# CONNECTEUR_2.net
KiCad netlist of a schematic drawn in Altium Designer
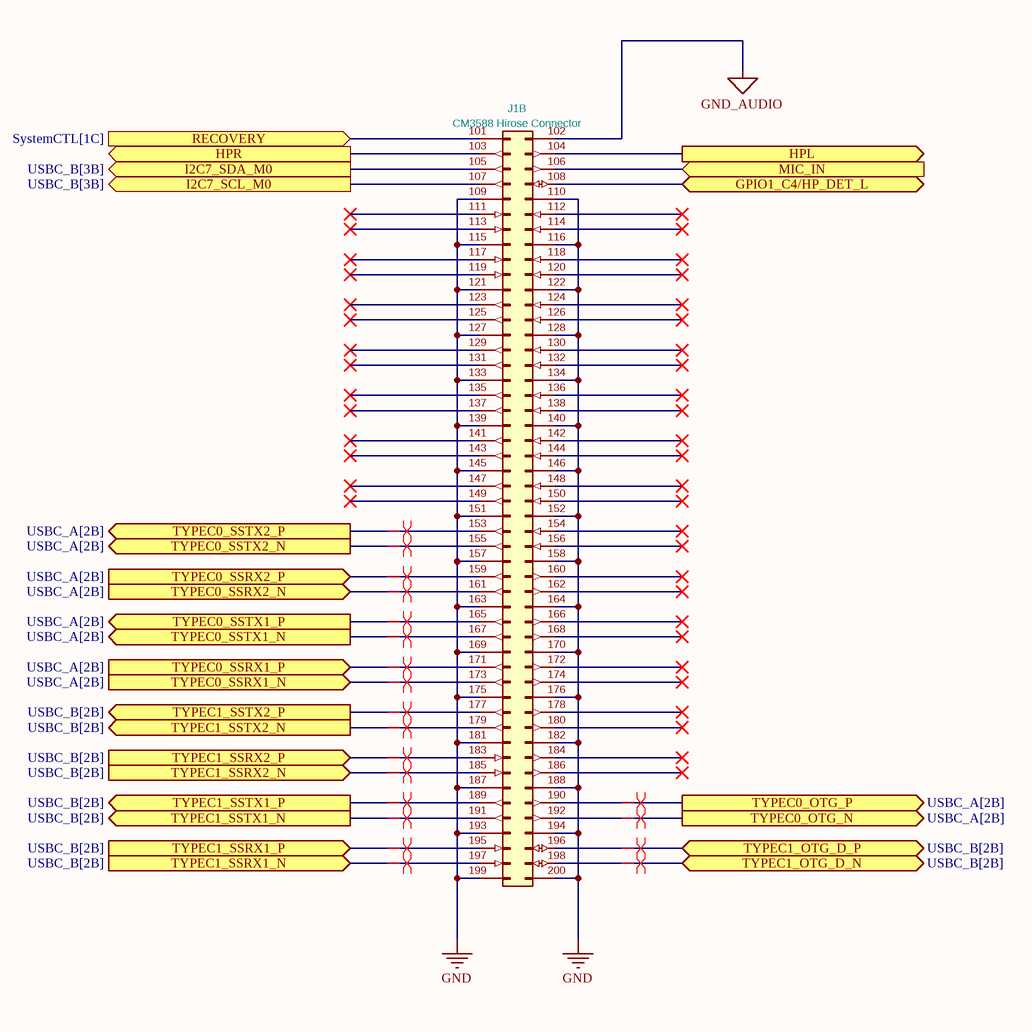
[diagram p0: CONNECTEUR_2.SchDoc, middle]

(export (version "E")
  (design (tool "Eeschema 10.0.6"))
  (components
    (comp (ref "J1")
      (value "CM3588 Hirose Connector")
      (footprint "CM3588")
      (libsource (lib "cm3588") (part "CM3588"))
    )
  )
  (nets
    (net (code "1") (name "/GPIO1_C4{slash}HP_DET_L") (class "Default")
      (node (ref "J1") (pin "108") (pinfunction "GPIO1_C4/HP_DET_L_108") (pintype "bidirectional"))
    )
    (net (code "2") (name "/HPL") (class "Default")
      (node (ref "J1") (pin "104") (pinfunction "HPL_104") (pintype "output"))
    )
    (net (code "3") (name "/HPR") (class "Default")
      (node (ref "J1") (pin "103") (pinfunction "HPR_103") (pintype "output"))
    )
    (net (code "4") (name "/I2C7_SCL_M0") (class "Default")
      (node (ref "J1") (pin "107") (pinfunction "I2C7_SCL_M0_107") (pintype "output"))
    )
    (net (code "5") (name "/I2C7_SDA_M0") (class "Default")
      (node (ref "J1") (pin "105") (pinfunction "I2C7_SDA_M0_105") (pintype "output"))
    )
    (net (code "6") (name "/MIC_IN") (class "Default")
      (node (ref "J1") (pin "106") (pinfunction "MIC_IN_106") (pintype "output"))
    )
    (net (code "7") (name "/RECOVERY") (class "Default")
      (node (ref "J1") (pin "101") (pinfunction "RECOVERY_101") (pintype "passive"))
    )
    (net (code "8") (name "/TYPEC0_OTG_N") (class "Default")
      (node (ref "J1") (pin "192") (pinfunction "TYPEC0_OTG_DM_192") (pintype "output"))
    )
    (net (code "9") (name "/TYPEC0_OTG_P") (class "Default")
      (node (ref "J1") (pin "190") (pinfunction "TYPEC0_OTG_DP_190") (pintype "output"))
    )
    (net (code "10") (name "/TYPEC0_SSRX1_N") (class "Default")
      (node (ref "J1") (pin "173") (pinfunction "TYPEC0_SSRX1N_173") (pintype "output"))
    )
    (net (code "11") (name "/TYPEC0_SSRX1_P") (class "Default")
      (node (ref "J1") (pin "171") (pinfunction "TYPEC0_SSRX1P_171") (pintype "output"))
    )
    (net (code "12") (name "/TYPEC0_SSRX2_N") (class "Default")
      (node (ref "J1") (pin "161") (pinfunction "TYPEC0_SSRX2N_161") (pintype "output"))
    )
    (net (code "13") (name "/TYPEC0_SSRX2_P") (class "Default")
      (node (ref "J1") (pin "159") (pinfunction "TYPEC0_SSRX2P_159") (pintype "output"))
    )
    (net (code "14") (name "/TYPEC0_SSTX1_N") (class "Default")
      (node (ref "J1") (pin "167") (pinfunction "TYPEC0_SSTX1N_167") (pintype "output"))
    )
    (net (code "15") (name "/TYPEC0_SSTX1_P") (class "Default")
      (node (ref "J1") (pin "165") (pinfunction "TYPEC0_SSTX1P_165") (pintype "output"))
    )
    (net (code "16") (name "/TYPEC0_SSTX2_N") (class "Default")
      (node (ref "J1") (pin "155") (pinfunction "TYPEC0_SSTX2N_155") (pintype "output"))
    )
    (net (code "17") (name "/TYPEC0_SSTX2_P") (class "Default")
      (node (ref "J1") (pin "153") (pinfunction "TYPEC0_SSTX2P_153") (pintype "output"))
    )
    (net (code "18") (name "/TYPEC1_OTG_D_N") (class "Default")
      (node (ref "J1") (pin "198") (pinfunction "TYPEC1_OTG_DM_198") (pintype "bidirectional"))
    )
    (net (code "19") (name "/TYPEC1_OTG_D_P") (class "Default")
      (node (ref "J1") (pin "196") (pinfunction "TYPEC1_OTG_DP_196") (pintype "bidirectional"))
    )
    (net (code "20") (name "/TYPEC1_SSRX1_N") (class "Default")
      (node (ref "J1") (pin "197") (pinfunction "TYPEC1_SSRX1N_197") (pintype "input"))
    )
    (net (code "21") (name "/TYPEC1_SSRX1_P") (class "Default")
      (node (ref "J1") (pin "195") (pinfunction "TYPEC1_SSRX1P_195") (pintype "input"))
    )
    (net (code "22") (name "/TYPEC1_SSRX2_N") (class "Default")
      (node (ref "J1") (pin "185") (pinfunction "TYPEC1_SSRX2N_185") (pintype "input"))
    )
    (net (code "23") (name "/TYPEC1_SSRX2_P") (class "Default")
      (node (ref "J1") (pin "183") (pinfunction "TYPEC1_SSRX2P_183") (pintype "input"))
    )
    (net (code "24") (name "/TYPEC1_SSTX1_N") (class "Default")
      (node (ref "J1") (pin "191") (pinfunction "TYPEC1_SSTX1N_191") (pintype "output"))
    )
    (net (code "25") (name "/TYPEC1_SSTX1_P") (class "Default")
      (node (ref "J1") (pin "189") (pinfunction "TYPEC1_SSTX1P_189") (pintype "output"))
    )
    (net (code "26") (name "/TYPEC1_SSTX2_N") (class "Default")
      (node (ref "J1") (pin "179") (pinfunction "TYPEC1_SSTX2N_179") (pintype "output"))
    )
    (net (code "27") (name "/TYPEC1_SSTX2_P") (class "Default")
      (node (ref "J1") (pin "177") (pinfunction "TYPEC1_SSTX2P_177") (pintype "output"))
    )
    (net (code "28") (name "GND") (class "Default")
      (node (ref "J1") (pin "109") (pinfunction "GND_109") (pintype "passive"))
      (node (ref "J1") (pin "110") (pinfunction "GND_110") (pintype "passive"))
      (node (ref "J1") (pin "115") (pinfunction "GND_115") (pintype "passive"))
      (node (ref "J1") (pin "116") (pinfunction "GND_116") (pintype "passive"))
      (node (ref "J1") (pin "121") (pinfunction "GND_121") (pintype "passive"))
      (node (ref "J1") (pin "122") (pinfunction "GND_122") (pintype "passive"))
      (node (ref "J1") (pin "127") (pinfunction "GND_127") (pintype "passive"))
      (node (ref "J1") (pin "128") (pinfunction "GND_128") (pintype "passive"))
      (node (ref "J1") (pin "133") (pinfunction "GND_133") (pintype "passive"))
      (node (ref "J1") (pin "134") (pinfunction "GND_134") (pintype "passive"))
      (node (ref "J1") (pin "139") (pinfunction "GND_139") (pintype "passive"))
      (node (ref "J1") (pin "140") (pinfunction "GND_140") (pintype "passive"))
      (node (ref "J1") (pin "145") (pinfunction "GND_145") (pintype "passive"))
      (node (ref "J1") (pin "146") (pinfunction "GND_146") (pintype "passive"))
      (node (ref "J1") (pin "151") (pinfunction "GND_151") (pintype "passive"))
      (node (ref "J1") (pin "152") (pinfunction "GND_152") (pintype "passive"))
      (node (ref "J1") (pin "157") (pinfunction "GND_157") (pintype "passive"))
      (node (ref "J1") (pin "158") (pinfunction "GND_158") (pintype "passive"))
      (node (ref "J1") (pin "163") (pinfunction "GND_163") (pintype "passive"))
      (node (ref "J1") (pin "164") (pinfunction "GND_164") (pintype "passive"))
      (node (ref "J1") (pin "169") (pinfunction "GND_169") (pintype "passive"))
      (node (ref "J1") (pin "170") (pinfunction "GND_170") (pintype "passive"))
      (node (ref "J1") (pin "175") (pinfunction "GND_175") (pintype "passive"))
      (node (ref "J1") (pin "176") (pinfunction "GND_176") (pintype "passive"))
      (node (ref "J1") (pin "181") (pinfunction "GND_181") (pintype "passive"))
      (node (ref "J1") (pin "182") (pinfunction "GND_182") (pintype "passive"))
      (node (ref "J1") (pin "187") (pinfunction "GND_187") (pintype "passive"))
      (node (ref "J1") (pin "188") (pinfunction "GND_188") (pintype "passive"))
      (node (ref "J1") (pin "193") (pinfunction "GND_193") (pintype "passive"))
      (node (ref "J1") (pin "194") (pinfunction "GND_194") (pintype "passive"))
      (node (ref "J1") (pin "199") (pinfunction "GND_199") (pintype "passive"))
      (node (ref "J1") (pin "200") (pinfunction "GND_200") (pintype "passive"))
    )
    (net (code "29") (name "GND_AUDIO") (class "Default")
      (node (ref "J1") (pin "102") (pinfunction "GND_AUDUO_102") (pintype "passive"))
    )
    (net (code "30") (name "unconnected-(J1B-MIPI_DPHY0_RX_CLKN-Pad120)") (class "Default")
      (node (ref "J1") (pin "120") (pinfunction "MIPI_DPHY0_RX_CLKN_120") (pintype "input+no_connect"))
    )
    (net (code "31") (name "unconnected-(J1B-MIPI_DPHY0_RX_CLKP-Pad118)") (class "Default")
      (node (ref "J1") (pin "118") (pinfunction "MIPI_DPHY0_RX_CLKP_118") (pintype "input+no_connect"))
    )
    (net (code "32") (name "unconnected-(J1B-MIPI_DPHY0_RX_D0N-Pad126)") (class "Default")
      (node (ref "J1") (pin "126") (pinfunction "MIPI_DPHY0_RX_D0N_126") (pintype "input+no_connect"))
    )
    (net (code "33") (name "unconnected-(J1B-MIPI_DPHY0_RX_D0P-Pad124)") (class "Default")
      (node (ref "J1") (pin "124") (pinfunction "MIPI_DPHY0_RX_D0P_124") (pintype "input+no_connect"))
    )
    (net (code "34") (name "unconnected-(J1B-MIPI_DPHY0_RX_D1N-Pad119)") (class "Default")
      (node (ref "J1") (pin "119") (pinfunction "MIPI_DPHY0_RX_D1N_119") (pintype "input+no_connect"))
    )
    (net (code "35") (name "unconnected-(J1B-MIPI_DPHY0_RX_D1P-Pad117)") (class "Default")
      (node (ref "J1") (pin "117") (pinfunction "MIPI_DPHY0_RX_D1P_117") (pintype "input+no_connect"))
    )
    (net (code "36") (name "unconnected-(J1B-MIPI_DPHY0_RX_D2N-Pad113)") (class "Default")
      (node (ref "J1") (pin "113") (pinfunction "MIPI_DPHY0_RX_D2N_113") (pintype "input+no_connect"))
    )
    (net (code "37") (name "unconnected-(J1B-MIPI_DPHY0_RX_D2P-Pad111)") (class "Default")
      (node (ref "J1") (pin "111") (pinfunction "MIPI_DPHY0_RX_D2P_111") (pintype "input+no_connect"))
    )
    (net (code "38") (name "unconnected-(J1B-MIPI_DPHY0_RX_D3N-Pad114)") (class "Default")
      (node (ref "J1") (pin "114") (pinfunction "MIPI_DPHY0_RX_D3N_114") (pintype "input+no_connect"))
    )
    (net (code "39") (name "unconnected-(J1B-MIPI_DPHY0_RX_D3P-Pad112)") (class "Default")
      (node (ref "J1") (pin "112") (pinfunction "MIPI_DPHY0_RX_D3P_112") (pintype "input+no_connect"))
    )
    (net (code "40") (name "unconnected-(J1B-MIPI_DPHY0_TX_CLKN-Pad137)") (class "Default")
      (node (ref "J1") (pin "137") (pinfunction "MIPI_DPHY0_TX_CLKN_137") (pintype "output+no_connect"))
    )
    (net (code "41") (name "unconnected-(J1B-MIPI_DPHY0_TX_CLKP-Pad135)") (class "Default")
      (node (ref "J1") (pin "135") (pinfunction "MIPI_DPHY0_TX_CLKP_135") (pintype "output+no_connect"))
    )
    (net (code "42") (name "unconnected-(J1B-MIPI_DPHY0_TX_D0N-Pad149)") (class "Default")
      (node (ref "J1") (pin "149") (pinfunction "MIPI_DPHY0_TX_D0N_149") (pintype "output+no_connect"))
    )
    (net (code "43") (name "unconnected-(J1B-MIPI_DPHY0_TX_D0P-Pad147)") (class "Default")
      (node (ref "J1") (pin "147") (pinfunction "MIPI_DPHY0_TX_D0P_147") (pintype "output+no_connect"))
    )
    (net (code "44") (name "unconnected-(J1B-MIPI_DPHY0_TX_D1N-Pad143)") (class "Default")
      (node (ref "J1") (pin "143") (pinfunction "MIPI_DPHY0_TX_D1N_143") (pintype "output+no_connect"))
    )
    (net (code "45") (name "unconnected-(J1B-MIPI_DPHY0_TX_D1P-Pad141)") (class "Default")
      (node (ref "J1") (pin "141") (pinfunction "MIPI_DPHY0_TX_D1P_141") (pintype "output+no_connect"))
    )
    (net (code "46") (name "unconnected-(J1B-MIPI_DPHY0_TX_D2N-Pad131)") (class "Default")
      (node (ref "J1") (pin "131") (pinfunction "MIPI_DPHY0_TX_D2N_131") (pintype "output+no_connect"))
    )
    (net (code "47") (name "unconnected-(J1B-MIPI_DPHY0_TX_D2P-Pad129)") (class "Default")
      (node (ref "J1") (pin "129") (pinfunction "MIPI_DPHY0_TX_D2P_129") (pintype "output+no_connect"))
    )
    (net (code "48") (name "unconnected-(J1B-MIPI_DPHY0_TX_D3N-Pad125)") (class "Default")
      (node (ref "J1") (pin "125") (pinfunction "MIPI_DPHY0_TX_D3N_125") (pintype "output+no_connect"))
    )
    (net (code "49") (name "unconnected-(J1B-MIPI_DPHY0_TX_D3P-Pad123)") (class "Default")
      (node (ref "J1") (pin "123") (pinfunction "MIPI_DPHY0_TX_D3P_123") (pintype "output+no_connect"))
    )
    (net (code "50") (name "unconnected-(J1B-MIPI_DPHY1_RX_CLKN-Pad144)") (class "Default")
      (node (ref "J1") (pin "144") (pinfunction "MIPI_DPHY1_RX_CLKN_144") (pintype "input+no_connect"))
    )
    (net (code "51") (name "unconnected-(J1B-MIPI_DPHY1_RX_CLKP-Pad142)") (class "Default")
      (node (ref "J1") (pin "142") (pinfunction "MIPI_DPHY1_RX_CLKP_142") (pintype "input+no_connect"))
    )
    (net (code "52") (name "unconnected-(J1B-MIPI_DPHY1_RX_D0N-Pad156)") (class "Default")
      (node (ref "J1") (pin "156") (pinfunction "MIPI_DPHY1_RX_D0N_156") (pintype "input+no_connect"))
    )
    (net (code "53") (name "unconnected-(J1B-MIPI_DPHY1_RX_D0P-Pad154)") (class "Default")
      (node (ref "J1") (pin "154") (pinfunction "MIPI_DPHY1_RX_D0P_154") (pintype "input+no_connect"))
    )
    (net (code "54") (name "unconnected-(J1B-MIPI_DPHY1_RX_D1N-Pad150)") (class "Default")
      (node (ref "J1") (pin "150") (pinfunction "MIPI_DPHY1_RX_D1N_150") (pintype "input+no_connect"))
    )
    (net (code "55") (name "unconnected-(J1B-MIPI_DPHY1_RX_D1P-Pad148)") (class "Default")
      (node (ref "J1") (pin "148") (pinfunction "MIPI_DPHY1_RX_D1P_148") (pintype "input+no_connect"))
    )
    (net (code "56") (name "unconnected-(J1B-MIPI_DPHY1_RX_D2N-Pad138)") (class "Default")
      (node (ref "J1") (pin "138") (pinfunction "MIPI_DPHY1_RX_D2N_138") (pintype "input+no_connect"))
    )
    (net (code "57") (name "unconnected-(J1B-MIPI_DPHY1_RX_D2P-Pad136)") (class "Default")
      (node (ref "J1") (pin "136") (pinfunction "MIPI_DPHY1_RX_D2P_136") (pintype "input+no_connect"))
    )
    (net (code "58") (name "unconnected-(J1B-MIPI_DPHY1_RX_D3N-Pad132)") (class "Default")
      (node (ref "J1") (pin "132") (pinfunction "MIPI_DPHY1_RX_D3N_132") (pintype "input+no_connect"))
    )
    (net (code "59") (name "unconnected-(J1B-MIPI_DPHY1_RX_D3P-Pad130)") (class "Default")
      (node (ref "J1") (pin "130") (pinfunction "MIPI_DPHY1_RX_D3P_130") (pintype "input+no_connect"))
    )
    (net (code "60") (name "unconnected-(J1B-MIPI_DPHY1_TX_CLKN-Pad174)") (class "Default")
      (node (ref "J1") (pin "174") (pinfunction "MIPI_DPHY1_TX_CLKN_174") (pintype "output+no_connect"))
    )
    (net (code "61") (name "unconnected-(J1B-MIPI_DPHY1_TX_CLKP-Pad172)") (class "Default")
      (node (ref "J1") (pin "172") (pinfunction "MIPI_DPHY1_TX_CLKP_172") (pintype "output+no_connect"))
    )
    (net (code "62") (name "unconnected-(J1B-MIPI_DPHY1_TX_D0N-Pad186)") (class "Default")
      (node (ref "J1") (pin "186") (pinfunction "MIPI_DPHY1_TX_D0N_186") (pintype "output+no_connect"))
    )
    (net (code "63") (name "unconnected-(J1B-MIPI_DPHY1_TX_D0P-Pad184)") (class "Default")
      (node (ref "J1") (pin "184") (pinfunction "MIPI_DPHY1_TX_D0P_184") (pintype "output+no_connect"))
    )
    (net (code "64") (name "unconnected-(J1B-MIPI_DPHY1_TX_D1N-Pad180)") (class "Default")
      (node (ref "J1") (pin "180") (pinfunction "MIPI_DPHY1_TX_D1N_180") (pintype "output+no_connect"))
    )
    (net (code "65") (name "unconnected-(J1B-MIPI_DPHY1_TX_D1P-Pad178)") (class "Default")
      (node (ref "J1") (pin "178") (pinfunction "MIPI_DPHY1_TX_D1P_178") (pintype "output+no_connect"))
    )
    (net (code "66") (name "unconnected-(J1B-MIPI_DPHY1_TX_D2N-Pad168)") (class "Default")
      (node (ref "J1") (pin "168") (pinfunction "MIPI_DPHY1_TX_D2N_168") (pintype "output+no_connect"))
    )
    (net (code "67") (name "unconnected-(J1B-MIPI_DPHY1_TX_D2P-Pad166)") (class "Default")
      (node (ref "J1") (pin "166") (pinfunction "MIPI_DPHY1_TX_D2P_166") (pintype "output+no_connect"))
    )
    (net (code "68") (name "unconnected-(J1B-MIPI_DPHY1_TX_D3N-Pad162)") (class "Default")
      (node (ref "J1") (pin "162") (pinfunction "MIPI_DPHY1_TX_D3N_162") (pintype "output+no_connect"))
    )
    (net (code "69") (name "unconnected-(J1B-MIPI_DPHY1_TX_D3P-Pad160)") (class "Default")
      (node (ref "J1") (pin "160") (pinfunction "MIPI_DPHY1_TX_D3P_160") (pintype "output+no_connect"))
    )
  )
)
